# motion_game.net
KiCad netlist of a schematic drawn in EAGLE
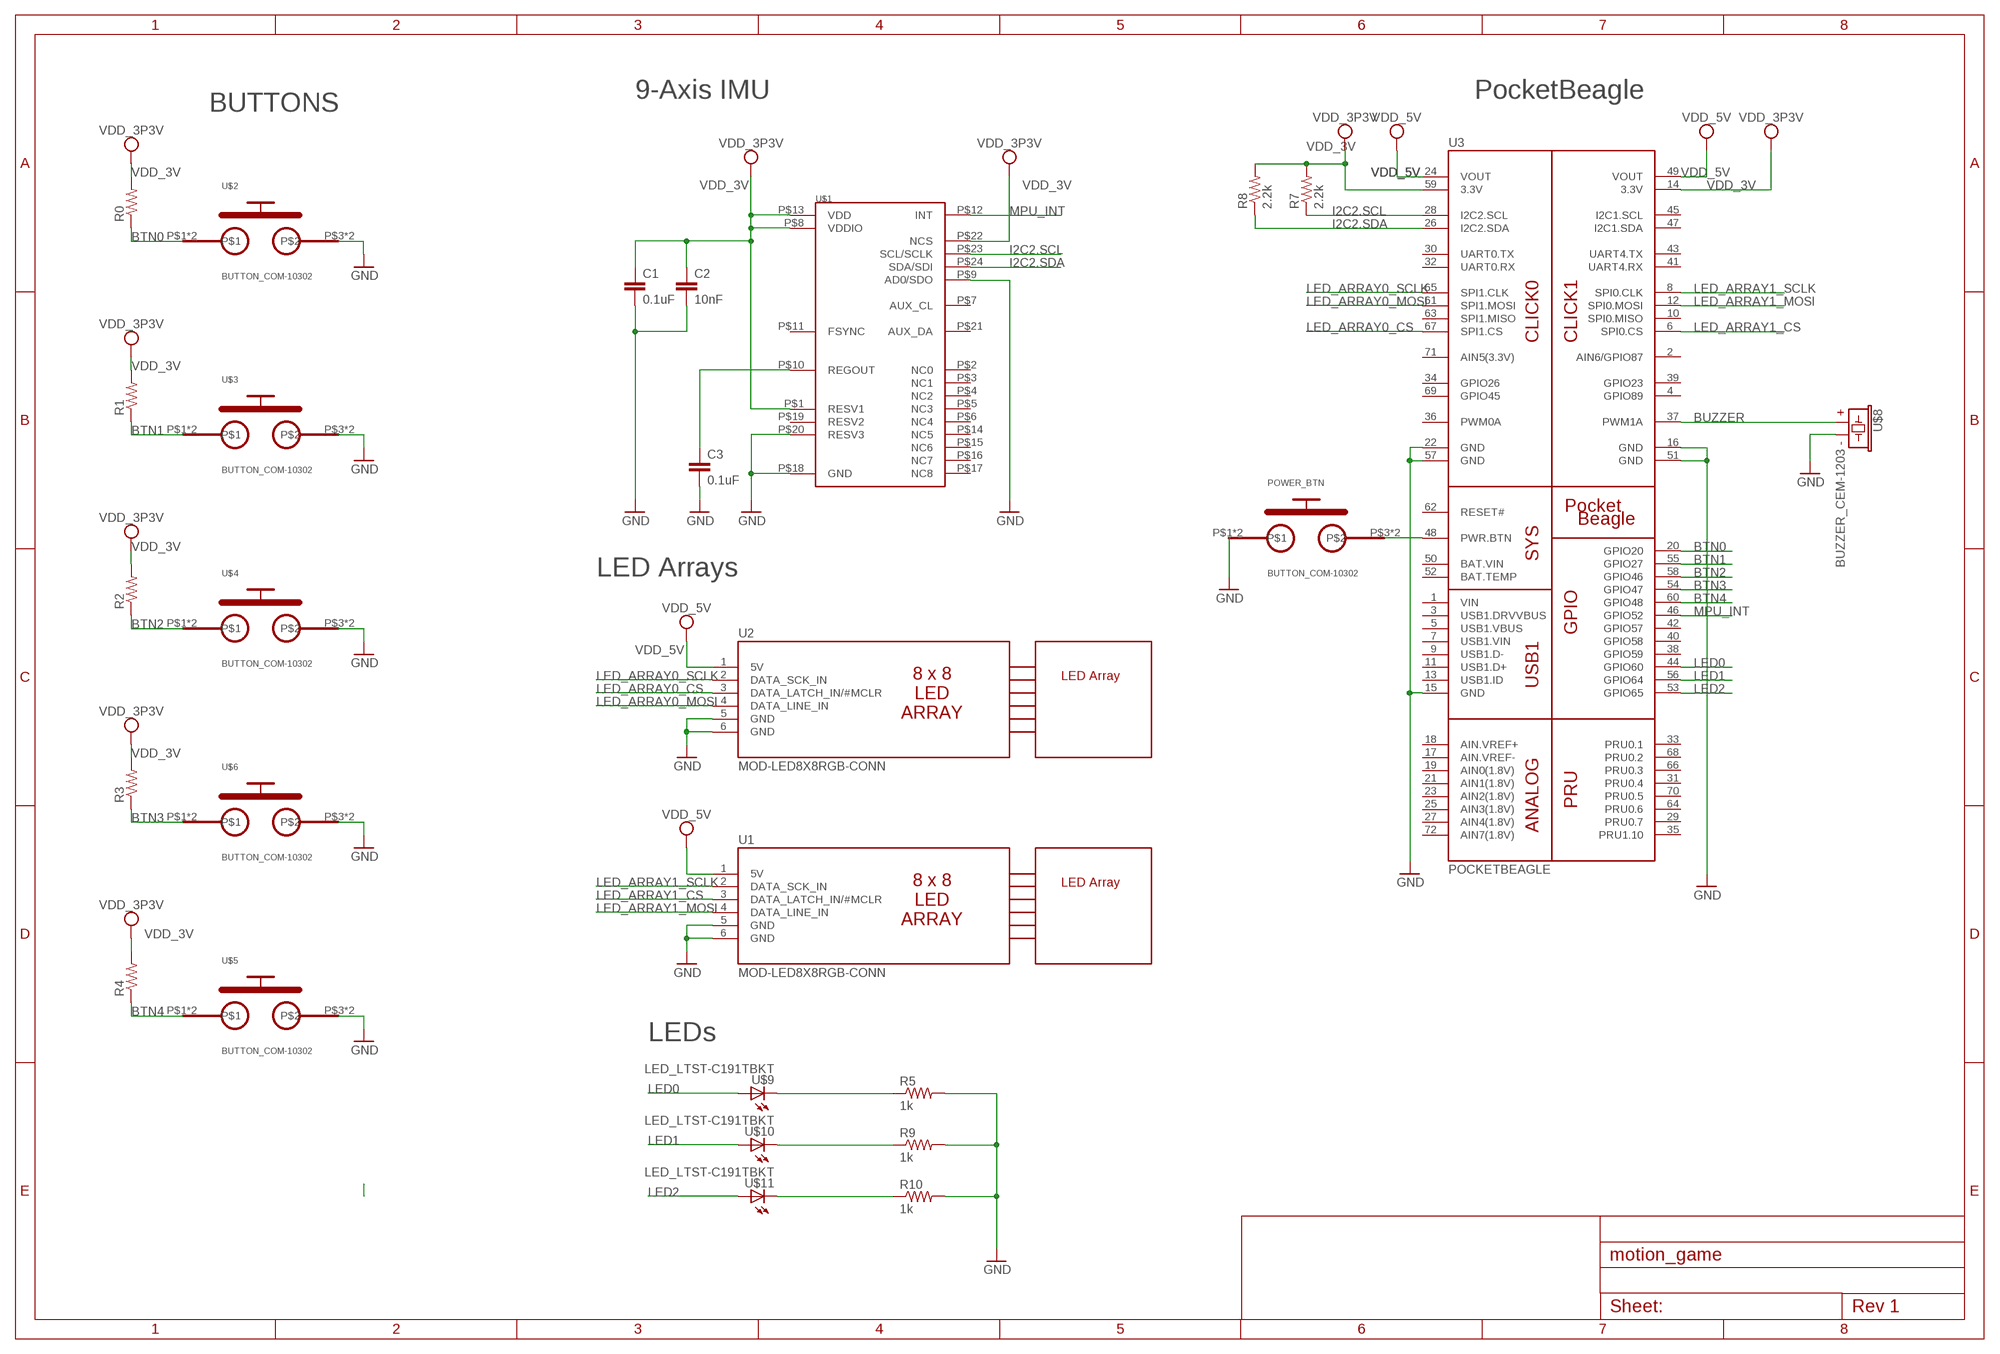
[diagram p0: schematic, sheet 1]

(export (version "E")
  (design (tool "Eeschema 10.0.6"))
  (components
    (comp (ref "C1")
      (value "0.1uF")
      (footprint "eagle-import:C0402")
      (libsource (lib "eagle-import") (part "C_C0402"))
    )
    (comp (ref "C2")
      (value "10nF")
      (footprint "eagle-import:C0402")
      (libsource (lib "eagle-import") (part "C_C0402"))
    )
    (comp (ref "C3")
      (value "0.1uF")
      (footprint "eagle-import:C0402")
      (libsource (lib "eagle-import") (part "C_C0402"))
    )
    (comp (ref "POWER_BTN")
      (value "BUTTON_COM-10302")
      (footprint "eagle-import:BUTTON_12.5MM")
      (libsource (lib "eagle-import") (part "BUTTON_COM-10302"))
    )
    (comp (ref "R0")
      (value "R_R0603")
      (footprint "eagle-import:R0603")
      (libsource (lib "eagle-import") (part "motion_game_R_R0603"))
    )
    (comp (ref "R1")
      (value "R_R0603")
      (footprint "eagle-import:R0603")
      (libsource (lib "eagle-import") (part "motion_game_R_R0603"))
    )
    (comp (ref "R2")
      (value "R_R0603")
      (footprint "eagle-import:R0603")
      (libsource (lib "eagle-import") (part "motion_game_R_R0603"))
    )
    (comp (ref "R3")
      (value "R_R0603")
      (footprint "eagle-import:R0603")
      (libsource (lib "eagle-import") (part "motion_game_R_R0603"))
    )
    (comp (ref "R4")
      (value "R_R0603")
      (footprint "eagle-import:R0603")
      (libsource (lib "eagle-import") (part "motion_game_R_R0603"))
    )
    (comp (ref "R5")
      (value "1k")
      (footprint "eagle-import:R0603")
      (libsource (lib "eagle-import") (part "R_R0603"))
    )
    (comp (ref "R7")
      (value "2.2k")
      (footprint "eagle-import:R0603")
      (libsource (lib "eagle-import") (part "motion_game_R_R0603"))
    )
    (comp (ref "R8")
      (value "2.2k")
      (footprint "eagle-import:R0603")
      (libsource (lib "eagle-import") (part "motion_game_R_R0603"))
    )
    (comp (ref "R9")
      (value "1k")
      (footprint "eagle-import:R0603")
      (libsource (lib "eagle-import") (part "R_R0603"))
    )
    (comp (ref "R10")
      (value "1k")
      (footprint "eagle-import:R0603")
      (libsource (lib "eagle-import") (part "R_R0603"))
    )
    (comp (ref "U$1")
      (value "MPU-9250")
      (footprint "eagle-import:QFN3X3MM")
      (libsource (lib "eagle-import") (part "MPU-9250"))
    )
    (comp (ref "U$2")
      (value "BUTTON_COM-10302")
      (footprint "eagle-import:BUTTON_12.5MM")
      (libsource (lib "eagle-import") (part "BUTTON_COM-10302"))
    )
    (comp (ref "U$3")
      (value "BUTTON_COM-10302")
      (footprint "eagle-import:BUTTON_12.5MM")
      (libsource (lib "eagle-import") (part "BUTTON_COM-10302"))
    )
    (comp (ref "U$4")
      (value "BUTTON_COM-10302")
      (footprint "eagle-import:BUTTON_12.5MM")
      (libsource (lib "eagle-import") (part "BUTTON_COM-10302"))
    )
    (comp (ref "U$5")
      (value "BUTTON_COM-10302")
      (footprint "eagle-import:BUTTON_12.5MM")
      (libsource (lib "eagle-import") (part "BUTTON_COM-10302"))
    )
    (comp (ref "U$6")
      (value "BUTTON_COM-10302")
      (footprint "eagle-import:BUTTON_12.5MM")
      (libsource (lib "eagle-import") (part "BUTTON_COM-10302"))
    )
    (comp (ref "U$7")
      (value "MOD-LED8X8RGB-OUTLINE")
      (footprint "eagle-import:MOD-LED8X8RGB")
      (libsource (lib "eagle-import") (part "MOD-LED8X8RGB-OUTLINE"))
    )
    (comp (ref "U$8")
      (value "BUZZER_CEM-1203")
      (footprint "eagle-import:BUZZER_6.5MM")
      (libsource (lib "eagle-import") (part "BUZZER_CEM-1203"))
    )
    (comp (ref "U$9")
      (value "LED_LTST-C191TBKT")
      (footprint "eagle-import:LED_EIA-STD")
      (libsource (lib "eagle-import") (part "LED_LTST-C191TBKT"))
    )
    (comp (ref "U$10")
      (value "LED_LTST-C191TBKT")
      (footprint "eagle-import:LED_EIA-STD")
      (libsource (lib "eagle-import") (part "LED_LTST-C191TBKT"))
    )
    (comp (ref "U$11")
      (value "LED_LTST-C191TBKT")
      (footprint "eagle-import:LED_EIA-STD")
      (libsource (lib "eagle-import") (part "LED_LTST-C191TBKT"))
    )
    (comp (ref "U$12")
      (value "MOD-LED8X8RGB-OUTLINE")
      (footprint "eagle-import:MOD-LED8X8RGB")
      (libsource (lib "eagle-import") (part "MOD-LED8X8RGB-OUTLINE"))
    )
    (comp (ref "U1")
      (value "MOD-LED8X8RGB-CONN")
      (footprint "eagle-import:FE06W")
      (libsource (lib "eagle-import") (part "MOD-LED8X8RGB-CONN"))
    )
    (comp (ref "U2")
      (value "MOD-LED8X8RGB-CONN")
      (footprint "eagle-import:FE06W")
      (libsource (lib "eagle-import") (part "MOD-LED8X8RGB-CONN"))
    )
    (comp (ref "U3")
      (value "POCKETBEAGLE")
      (footprint "eagle-import:POCKETBEAGLE")
      (libsource (lib "eagle-import") (part "POCKETBEAGLE"))
    )
  )
  (nets
    (net (code "1") (name "/BTN0") (class "Default")
      (node (ref "R0") (pin "1") (pinfunction "1_1") (pintype "passive"))
      (node (ref "U$2") (pin "P$1") (pinfunction "P$1_P$1") (pintype "bidirectional"))
      (node (ref "U$2") (pin "P$2") (pinfunction "P$1_P$2") (pintype "bidirectional"))
      (node (ref "U3") (pin "20") (pinfunction "GPIO20_20") (pintype "bidirectional"))
    )
    (net (code "2") (name "/BTN1") (class "Default")
      (node (ref "R1") (pin "1") (pinfunction "1_1") (pintype "passive"))
      (node (ref "U$3") (pin "P$1") (pinfunction "P$1_P$1") (pintype "bidirectional"))
      (node (ref "U$3") (pin "P$2") (pinfunction "P$1_P$2") (pintype "bidirectional"))
      (node (ref "U3") (pin "55") (pinfunction "GPIO27_55") (pintype "bidirectional"))
    )
    (net (code "3") (name "/BTN2") (class "Default")
      (node (ref "R2") (pin "1") (pinfunction "1_1") (pintype "passive"))
      (node (ref "U$4") (pin "P$1") (pinfunction "P$1_P$1") (pintype "bidirectional"))
      (node (ref "U$4") (pin "P$2") (pinfunction "P$1_P$2") (pintype "bidirectional"))
      (node (ref "U3") (pin "58") (pinfunction "GPIO46_58") (pintype "bidirectional"))
    )
    (net (code "4") (name "/BTN3") (class "Default")
      (node (ref "R3") (pin "1") (pinfunction "1_1") (pintype "passive"))
      (node (ref "U$6") (pin "P$1") (pinfunction "P$1_P$1") (pintype "bidirectional"))
      (node (ref "U$6") (pin "P$2") (pinfunction "P$1_P$2") (pintype "bidirectional"))
      (node (ref "U3") (pin "54") (pinfunction "GPIO47_54") (pintype "bidirectional"))
    )
    (net (code "5") (name "/BTN4") (class "Default")
      (node (ref "R4") (pin "1") (pinfunction "1_1") (pintype "passive"))
      (node (ref "U$5") (pin "P$1") (pinfunction "P$1_P$1") (pintype "bidirectional"))
      (node (ref "U$5") (pin "P$2") (pinfunction "P$1_P$2") (pintype "bidirectional"))
      (node (ref "U3") (pin "60") (pinfunction "GPIO48_60") (pintype "bidirectional"))
    )
    (net (code "6") (name "/BUZZER") (class "Default")
      (node (ref "U$8") (pin "P$2") (pinfunction "1_P$2") (pintype "passive"))
      (node (ref "U3") (pin "37") (pinfunction "PWM1A_37") (pintype "bidirectional"))
    )
    (net (code "7") (name "/I2C2.SCL") (class "Default")
      (node (ref "R7") (pin "1") (pinfunction "1_1") (pintype "passive"))
      (node (ref "U$1") (pin "P$23") (pinfunction "SCL/SCLK_P$23") (pintype "bidirectional"))
      (node (ref "U3") (pin "28") (pinfunction "I2C2.SCL_28") (pintype "bidirectional"))
    )
    (net (code "8") (name "/I2C2.SDA") (class "Default")
      (node (ref "R8") (pin "1") (pinfunction "1_1") (pintype "passive"))
      (node (ref "U$1") (pin "P$24") (pinfunction "SDA/SDI_P$24") (pintype "bidirectional"))
      (node (ref "U3") (pin "26") (pinfunction "I2C2.SDA_26") (pintype "bidirectional"))
    )
    (net (code "9") (name "/LED0") (class "Default")
      (node (ref "U$9") (pin "P$1") (pinfunction "A_P$1") (pintype "passive"))
      (node (ref "U3") (pin "44") (pinfunction "GPIO60_44") (pintype "bidirectional"))
    )
    (net (code "10") (name "/LED1") (class "Default")
      (node (ref "U$10") (pin "P$1") (pinfunction "A_P$1") (pintype "passive"))
      (node (ref "U3") (pin "56") (pinfunction "GPIO64_56") (pintype "bidirectional"))
    )
    (net (code "11") (name "/LED2") (class "Default")
      (node (ref "U$11") (pin "P$1") (pinfunction "A_P$1") (pintype "passive"))
      (node (ref "U3") (pin "53") (pinfunction "GPIO65_53") (pintype "bidirectional"))
    )
    (net (code "12") (name "/LED_ARRAY0_CS") (class "Default")
      (node (ref "U2") (pin "3") (pinfunction "DATA_LATCH_IN/#MCLR_3") (pintype "bidirectional"))
      (node (ref "U3") (pin "67") (pinfunction "SPI1.CS_67") (pintype "bidirectional"))
    )
    (net (code "13") (name "/LED_ARRAY0_MOSI") (class "Default")
      (node (ref "U2") (pin "4") (pinfunction "DATA_LINE_IN_4") (pintype "bidirectional"))
      (node (ref "U3") (pin "61") (pinfunction "SPI1.MOSI_61") (pintype "bidirectional"))
    )
    (net (code "14") (name "/LED_ARRAY0_SCLK") (class "Default")
      (node (ref "U2") (pin "2") (pinfunction "DATA_SCK_IN_2") (pintype "bidirectional"))
      (node (ref "U3") (pin "65") (pinfunction "SPI1.CLK_65") (pintype "bidirectional"))
    )
    (net (code "15") (name "/LED_ARRAY1_CS") (class "Default")
      (node (ref "U1") (pin "3") (pinfunction "DATA_LATCH_IN/#MCLR_3") (pintype "bidirectional"))
      (node (ref "U3") (pin "6") (pinfunction "SPI0.CS_6") (pintype "bidirectional"))
    )
    (net (code "16") (name "/LED_ARRAY1_MOSI") (class "Default")
      (node (ref "U1") (pin "4") (pinfunction "DATA_LINE_IN_4") (pintype "bidirectional"))
      (node (ref "U3") (pin "12") (pinfunction "SPI0.MOSI_12") (pintype "bidirectional"))
    )
    (net (code "17") (name "/LED_ARRAY1_SCLK") (class "Default")
      (node (ref "U1") (pin "2") (pinfunction "DATA_SCK_IN_2") (pintype "bidirectional"))
      (node (ref "U3") (pin "8") (pinfunction "SPI0.CLK_8") (pintype "bidirectional"))
    )
    (net (code "18") (name "/MPU_INT") (class "Default")
      (node (ref "U$1") (pin "P$12") (pinfunction "INT_P$12") (pintype "bidirectional"))
      (node (ref "U3") (pin "46") (pinfunction "GPIO52_46") (pintype "bidirectional"))
    )
    (net (code "19") (name "GND") (class "Default")
      (node (ref "C1") (pin "2") (pinfunction "2_2") (pintype "passive"))
      (node (ref "C2") (pin "2") (pinfunction "2_2") (pintype "passive"))
      (node (ref "C3") (pin "2") (pinfunction "2_2") (pintype "passive"))
      (node (ref "POWER_BTN") (pin "P$1") (pinfunction "P$1_P$1") (pintype "bidirectional"))
      (node (ref "POWER_BTN") (pin "P$2") (pinfunction "P$1_P$2") (pintype "bidirectional"))
      (node (ref "R10") (pin "2") (pinfunction "2_2") (pintype "passive"))
      (node (ref "R5") (pin "2") (pinfunction "2_2") (pintype "passive"))
      (node (ref "R9") (pin "2") (pinfunction "2_2") (pintype "passive"))
      (node (ref "U$1") (pin "P$18") (pinfunction "GND_P$18") (pintype "bidirectional"))
      (node (ref "U$1") (pin "P$20") (pinfunction "RESV3_P$20") (pintype "bidirectional"))
      (node (ref "U$1") (pin "P$9") (pinfunction "AD0/SDO_P$9") (pintype "bidirectional"))
      (node (ref "U$2") (pin "P$3") (pinfunction "P$2_P$3") (pintype "bidirectional"))
      (node (ref "U$2") (pin "P$4") (pinfunction "P$2_P$4") (pintype "bidirectional"))
      (node (ref "U$3") (pin "P$3") (pinfunction "P$2_P$3") (pintype "bidirectional"))
      (node (ref "U$3") (pin "P$4") (pinfunction "P$2_P$4") (pintype "bidirectional"))
      (node (ref "U$4") (pin "P$3") (pinfunction "P$2_P$3") (pintype "bidirectional"))
      (node (ref "U$4") (pin "P$4") (pinfunction "P$2_P$4") (pintype "bidirectional"))
      (node (ref "U$5") (pin "P$3") (pinfunction "P$2_P$3") (pintype "bidirectional"))
      (node (ref "U$5") (pin "P$4") (pinfunction "P$2_P$4") (pintype "bidirectional"))
      (node (ref "U$6") (pin "P$3") (pinfunction "P$2_P$3") (pintype "bidirectional"))
      (node (ref "U$6") (pin "P$4") (pinfunction "P$2_P$4") (pintype "bidirectional"))
      (node (ref "U$8") (pin "P$1") (pinfunction "2_P$1") (pintype "passive"))
      (node (ref "U1") (pin "5") (pinfunction "GND_5") (pintype "bidirectional"))
      (node (ref "U1") (pin "6") (pinfunction "GND_6") (pintype "bidirectional"))
      (node (ref "U2") (pin "5") (pinfunction "GND_5") (pintype "bidirectional"))
      (node (ref "U2") (pin "6") (pinfunction "GND_6") (pintype "bidirectional"))
      (node (ref "U3") (pin "15") (pinfunction "GND_15") (pintype "bidirectional"))
      (node (ref "U3") (pin "16") (pinfunction "GND_16") (pintype "bidirectional"))
      (node (ref "U3") (pin "22") (pinfunction "GND_22") (pintype "bidirectional"))
      (node (ref "U3") (pin "51") (pinfunction "GND_51") (pintype "bidirectional"))
      (node (ref "U3") (pin "57") (pinfunction "GND_57") (pintype "bidirectional"))
    )
    (net (code "20") (name "Net-(U$1-REGOUT)") (class "Default")
      (node (ref "C3") (pin "1") (pinfunction "1_1") (pintype "passive"))
      (node (ref "U$1") (pin "P$10") (pinfunction "REGOUT_P$10") (pintype "bidirectional"))
    )
    (net (code "21") (name "Net-(U$9-C)") (class "Default")
      (node (ref "R5") (pin "1") (pinfunction "1_1") (pintype "passive"))
      (node (ref "U$9") (pin "P$2") (pinfunction "C_P$2") (pintype "passive"))
    )
    (net (code "22") (name "Net-(U$10-C)") (class "Default")
      (node (ref "R9") (pin "1") (pinfunction "1_1") (pintype "passive"))
      (node (ref "U$10") (pin "P$2") (pinfunction "C_P$2") (pintype "passive"))
    )
    (net (code "23") (name "Net-(U$11-C)") (class "Default")
      (node (ref "R10") (pin "1") (pinfunction "1_1") (pintype "passive"))
      (node (ref "U$11") (pin "P$2") (pinfunction "C_P$2") (pintype "passive"))
    )
    (net (code "24") (name "Net-(U3-PWR.BTN)") (class "Default")
      (node (ref "POWER_BTN") (pin "P$3") (pinfunction "P$2_P$3") (pintype "bidirectional"))
      (node (ref "POWER_BTN") (pin "P$4") (pinfunction "P$2_P$4") (pintype "bidirectional"))
      (node (ref "U3") (pin "48") (pinfunction "PWR.BTN_48") (pintype "bidirectional"))
    )
    (net (code "25") (name "VDD_3P3V") (class "Default")
      (node (ref "C1") (pin "1") (pinfunction "1_1") (pintype "passive"))
      (node (ref "C2") (pin "1") (pinfunction "1_1") (pintype "passive"))
      (node (ref "R0") (pin "2") (pinfunction "2_2") (pintype "passive"))
      (node (ref "R1") (pin "2") (pinfunction "2_2") (pintype "passive"))
      (node (ref "R2") (pin "2") (pinfunction "2_2") (pintype "passive"))
      (node (ref "R3") (pin "2") (pinfunction "2_2") (pintype "passive"))
      (node (ref "R4") (pin "2") (pinfunction "2_2") (pintype "passive"))
      (node (ref "R7") (pin "2") (pinfunction "2_2") (pintype "passive"))
      (node (ref "R8") (pin "2") (pinfunction "2_2") (pintype "passive"))
      (node (ref "U$1") (pin "P$1") (pinfunction "RESV1_P$1") (pintype "bidirectional"))
      (node (ref "U$1") (pin "P$13") (pinfunction "VDD_P$13") (pintype "bidirectional"))
      (node (ref "U$1") (pin "P$22") (pinfunction "NCS_P$22") (pintype "bidirectional"))
      (node (ref "U$1") (pin "P$8") (pinfunction "VDDIO_P$8") (pintype "bidirectional"))
      (node (ref "U3") (pin "14") (pinfunction "3.3V_14") (pintype "bidirectional"))
      (node (ref "U3") (pin "59") (pinfunction "3.3V_59") (pintype "bidirectional"))
    )
    (net (code "26") (name "VDD_5V") (class "Default")
      (node (ref "U1") (pin "1") (pinfunction "5V_1") (pintype "bidirectional"))
      (node (ref "U2") (pin "1") (pinfunction "5V_1") (pintype "bidirectional"))
      (node (ref "U3") (pin "24") (pinfunction "VOUT_24") (pintype "bidirectional"))
      (node (ref "U3") (pin "49") (pinfunction "VOUT_49") (pintype "bidirectional"))
    )
    (net (code "27") (name "unconnected-(U$1-AUX_CL-PadP$7)") (class "Default")
      (node (ref "U$1") (pin "P$7") (pinfunction "AUX_CL_P$7") (pintype "bidirectional"))
    )
    (net (code "28") (name "unconnected-(U$1-AUX_DA-PadP$21)") (class "Default")
      (node (ref "U$1") (pin "P$21") (pinfunction "AUX_DA_P$21") (pintype "bidirectional"))
    )
    (net (code "29") (name "unconnected-(U$1-FSYNC-PadP$11)") (class "Default")
      (node (ref "U$1") (pin "P$11") (pinfunction "FSYNC_P$11") (pintype "bidirectional"))
    )
    (net (code "30") (name "unconnected-(U$1-NC0-PadP$2)") (class "Default")
      (node (ref "U$1") (pin "P$2") (pinfunction "NC0_P$2") (pintype "bidirectional"))
    )
    (net (code "31") (name "unconnected-(U$1-NC1-PadP$3)") (class "Default")
      (node (ref "U$1") (pin "P$3") (pinfunction "NC1_P$3") (pintype "bidirectional"))
    )
    (net (code "32") (name "unconnected-(U$1-NC2-PadP$4)") (class "Default")
      (node (ref "U$1") (pin "P$4") (pinfunction "NC2_P$4") (pintype "bidirectional"))
    )
    (net (code "33") (name "unconnected-(U$1-NC3-PadP$5)") (class "Default")
      (node (ref "U$1") (pin "P$5") (pinfunction "NC3_P$5") (pintype "bidirectional"))
    )
    (net (code "34") (name "unconnected-(U$1-NC4-PadP$6)") (class "Default")
      (node (ref "U$1") (pin "P$6") (pinfunction "NC4_P$6") (pintype "bidirectional"))
    )
    (net (code "35") (name "unconnected-(U$1-NC5-PadP$14)") (class "Default")
      (node (ref "U$1") (pin "P$14") (pinfunction "NC5_P$14") (pintype "bidirectional"))
    )
    (net (code "36") (name "unconnected-(U$1-NC6-PadP$15)") (class "Default")
      (node (ref "U$1") (pin "P$15") (pinfunction "NC6_P$15") (pintype "bidirectional"))
    )
    (net (code "37") (name "unconnected-(U$1-NC7-PadP$16)") (class "Default")
      (node (ref "U$1") (pin "P$16") (pinfunction "NC7_P$16") (pintype "bidirectional"))
    )
    (net (code "38") (name "unconnected-(U$1-NC8-PadP$17)") (class "Default")
      (node (ref "U$1") (pin "P$17") (pinfunction "NC8_P$17") (pintype "bidirectional"))
    )
    (net (code "39") (name "unconnected-(U$1-RESV2-PadP$19)") (class "Default")
      (node (ref "U$1") (pin "P$19") (pinfunction "RESV2_P$19") (pintype "bidirectional"))
    )
    (net (code "40") (name "unconnected-(U3-AIN.VREF+-Pad18)") (class "Default")
      (node (ref "U3") (pin "18") (pinfunction "AIN.VREF+_18") (pintype "bidirectional"))
    )
    (net (code "41") (name "unconnected-(U3-AIN.VREF--Pad17)") (class "Default")
      (node (ref "U3") (pin "17") (pinfunction "AIN.VREF-_17") (pintype "bidirectional"))
    )
    (net (code "42") (name "unconnected-(U3-AIN0(1.8V)-Pad19)") (class "Default")
      (node (ref "U3") (pin "19") (pinfunction "AIN0(1.8V)_19") (pintype "bidirectional"))
    )
    (net (code "43") (name "unconnected-(U3-AIN1(1.8V)-Pad21)") (class "Default")
      (node (ref "U3") (pin "21") (pinfunction "AIN1(1.8V)_21") (pintype "bidirectional"))
    )
    (net (code "44") (name "unconnected-(U3-AIN2(1.8V)-Pad23)") (class "Default")
      (node (ref "U3") (pin "23") (pinfunction "AIN2(1.8V)_23") (pintype "bidirectional"))
    )
    (net (code "45") (name "unconnected-(U3-AIN3(1.8V)-Pad25)") (class "Default")
      (node (ref "U3") (pin "25") (pinfunction "AIN3(1.8V)_25") (pintype "bidirectional"))
    )
    (net (code "46") (name "unconnected-(U3-AIN4(1.8V)-Pad27)") (class "Default")
      (node (ref "U3") (pin "27") (pinfunction "AIN4(1.8V)_27") (pintype "bidirectional"))
    )
    (net (code "47") (name "unconnected-(U3-AIN5(3.3V)-Pad71)") (class "Default")
      (node (ref "U3") (pin "71") (pinfunction "AIN5(3.3V)_71") (pintype "bidirectional"))
    )
    (net (code "48") (name "unconnected-(U3-AIN6{slash}GPIO87-Pad2)") (class "Default")
      (node (ref "U3") (pin "2") (pinfunction "AIN6/GPIO87_2") (pintype "bidirectional"))
    )
    (net (code "49") (name "unconnected-(U3-AIN7(1.8V)-Pad72)") (class "Default")
      (node (ref "U3") (pin "72") (pinfunction "AIN7(1.8V)_72") (pintype "bidirectional"))
    )
    (net (code "50") (name "unconnected-(U3-BAT.TEMP-Pad52)") (class "Default")
      (node (ref "U3") (pin "52") (pinfunction "BAT.TEMP_52") (pintype "bidirectional"))
    )
    (net (code "51") (name "unconnected-(U3-BAT.VIN-Pad50)") (class "Default")
      (node (ref "U3") (pin "50") (pinfunction "BAT.VIN_50") (pintype "bidirectional"))
    )
    (net (code "52") (name "unconnected-(U3-GPIO23-Pad39)") (class "Default")
      (node (ref "U3") (pin "39") (pinfunction "GPIO23_39") (pintype "bidirectional"))
    )
    (net (code "53") (name "unconnected-(U3-GPIO26-Pad34)") (class "Default")
      (node (ref "U3") (pin "34") (pinfunction "GPIO26_34") (pintype "bidirectional"))
    )
    (net (code "54") (name "unconnected-(U3-GPIO45-Pad69)") (class "Default")
      (node (ref "U3") (pin "69") (pinfunction "GPIO45_69") (pintype "bidirectional"))
    )
    (net (code "55") (name "unconnected-(U3-GPIO57-Pad42)") (class "Default")
      (node (ref "U3") (pin "42") (pinfunction "GPIO57_42") (pintype "bidirectional"))
    )
    (net (code "56") (name "unconnected-(U3-GPIO58-Pad40)") (class "Default")
      (node (ref "U3") (pin "40") (pinfunction "GPIO58_40") (pintype "bidirectional"))
    )
    (net (code "57") (name "unconnected-(U3-GPIO59-Pad38)") (class "Default")
      (node (ref "U3") (pin "38") (pinfunction "GPIO59_38") (pintype "bidirectional"))
    )
    (net (code "58") (name "unconnected-(U3-GPIO89-Pad4)") (class "Default")
      (node (ref "U3") (pin "4") (pinfunction "GPIO89_4") (pintype "bidirectional"))
    )
    (net (code "59") (name "unconnected-(U3-I2C1.SCL-Pad45)") (class "Default")
      (node (ref "U3") (pin "45") (pinfunction "I2C1.SCL_45") (pintype "bidirectional"))
    )
    (net (code "60") (name "unconnected-(U3-I2C1.SDA-Pad47)") (class "Default")
      (node (ref "U3") (pin "47") (pinfunction "I2C1.SDA_47") (pintype "bidirectional"))
    )
    (net (code "61") (name "unconnected-(U3-PRU0.1-Pad33)") (class "Default")
      (node (ref "U3") (pin "33") (pinfunction "PRU0.1_33") (pintype "bidirectional"))
    )
    (net (code "62") (name "unconnected-(U3-PRU0.2-Pad68)") (class "Default")
      (node (ref "U3") (pin "68") (pinfunction "PRU0.2_68") (pintype "bidirectional"))
    )
    (net (code "63") (name "unconnected-(U3-PRU0.3-Pad66)") (class "Default")
      (node (ref "U3") (pin "66") (pinfunction "PRU0.3_66") (pintype "bidirectional"))
    )
    (net (code "64") (name "unconnected-(U3-PRU0.4-Pad31)") (class "Default")
      (node (ref "U3") (pin "31") (pinfunction "PRU0.4_31") (pintype "bidirectional"))
    )
    (net (code "65") (name "unconnected-(U3-PRU0.5-Pad70)") (class "Default")
      (node (ref "U3") (pin "70") (pinfunction "PRU0.5_70") (pintype "bidirectional"))
    )
    (net (code "66") (name "unconnected-(U3-PRU0.6-Pad64)") (class "Default")
      (node (ref "U3") (pin "64") (pinfunction "PRU0.6_64") (pintype "bidirectional"))
    )
    (net (code "67") (name "unconnected-(U3-PRU0.7-Pad29)") (class "Default")
      (node (ref "U3") (pin "29") (pinfunction "PRU0.7_29") (pintype "bidirectional"))
    )
    (net (code "68") (name "unconnected-(U3-PRU1.10-Pad35)") (class "Default")
      (node (ref "U3") (pin "35") (pinfunction "PRU1.10_35") (pintype "bidirectional"))
    )
    (net (code "69") (name "unconnected-(U3-PWM0A-Pad36)") (class "Default")
      (node (ref "U3") (pin "36") (pinfunction "PWM0A_36") (pintype "bidirectional"))
    )
    (net (code "70") (name "unconnected-(U3-RESET#-Pad62)") (class "Default")
      (node (ref "U3") (pin "62") (pinfunction "RESET#_62") (pintype "bidirectional"))
    )
    (net (code "71") (name "unconnected-(U3-SPI0.MISO-Pad10)") (class "Default")
      (node (ref "U3") (pin "10") (pinfunction "SPI0.MISO_10") (pintype "bidirectional"))
    )
    (net (code "72") (name "unconnected-(U3-SPI1.MISO-Pad63)") (class "Default")
      (node (ref "U3") (pin "63") (pinfunction "SPI1.MISO_63") (pintype "bidirectional"))
    )
    (net (code "73") (name "unconnected-(U3-UART0.RX-Pad32)") (class "Default")
      (node (ref "U3") (pin "32") (pinfunction "UART0.RX_32") (pintype "bidirectional"))
    )
    (net (code "74") (name "unconnected-(U3-UART0.TX-Pad30)") (class "Default")
      (node (ref "U3") (pin "30") (pinfunction "UART0.TX_30") (pintype "bidirectional"))
    )
    (net (code "75") (name "unconnected-(U3-UART4.RX-Pad41)") (class "Default")
      (node (ref "U3") (pin "41") (pinfunction "UART4.RX_41") (pintype "bidirectional"))
    )
    (net (code "76") (name "unconnected-(U3-UART4.TX-Pad43)") (class "Default")
      (node (ref "U3") (pin "43") (pinfunction "UART4.TX_43") (pintype "bidirectional"))
    )
    (net (code "77") (name "unconnected-(U3-USB1.D+-Pad11)") (class "Default")
      (node (ref "U3") (pin "11") (pinfunction "USB1.D+_11") (pintype "bidirectional"))
    )
    (net (code "78") (name "unconnected-(U3-USB1.D--Pad9)") (class "Default")
      (node (ref "U3") (pin "9") (pinfunction "USB1.D-_9") (pintype "bidirectional"))
    )
    (net (code "79") (name "unconnected-(U3-USB1.DRVVBUS-Pad3)") (class "Default")
      (node (ref "U3") (pin "3") (pinfunction "USB1.DRVVBUS_3") (pintype "bidirectional"))
    )
    (net (code "80") (name "unconnected-(U3-USB1.ID-Pad13)") (class "Default")
      (node (ref "U3") (pin "13") (pinfunction "USB1.ID_13") (pintype "bidirectional"))
    )
    (net (code "81") (name "unconnected-(U3-USB1.VBUS-Pad5)") (class "Default")
      (node (ref "U3") (pin "5") (pinfunction "USB1.VBUS_5") (pintype "bidirectional"))
    )
    (net (code "82") (name "unconnected-(U3-USB1.VIN-Pad7)") (class "Default")
      (node (ref "U3") (pin "7") (pinfunction "USB1.VIN_7") (pintype "bidirectional"))
    )
    (net (code "83") (name "unconnected-(U3-VIN-Pad1)") (class "Default")
      (node (ref "U3") (pin "1") (pinfunction "VIN_1") (pintype "bidirectional"))
    )
  )
)
